# 15V_PowerSupply.net
KiCad netlist of a schematic drawn in Altium Designer
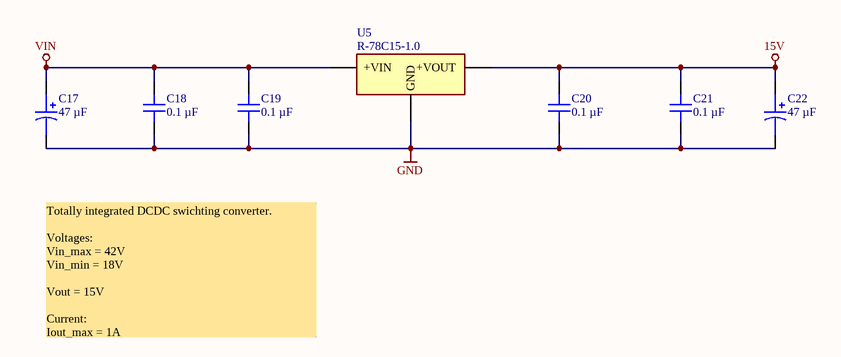
[diagram p0: 15V_PowerSupply.SchDoc]

(export (version "E")
  (design (tool "Eeschema 10.0.6"))
  (components
    (comp (ref "C17")
      (value "47 µF")
      (footprint "CAPAE830X650N")
      (description "Capacitor, 47µF, 35VDC Al Electrolyt")
      (fields
        (field (name "MANUFACTURER PART NUMBER") "EEE-1VA470P")
        (field (name "MANUFACTURER") "Panasonic")
        (field (name "CREATED FROM") "T. Wendt")
      )
      (libsource (lib "user") (part "CAPACITOR_POLARIZED_EEE"))
    )
    (comp (ref "C18")
      (value "0.1 µF")
      (footprint "C_0603")
      (description "Capacitor 0603, 50 VDC, 0.1 µF, X7R")
      (fields
        (field (name "MANUFACTURER PART NUMBER") "C0603X104K5RAC7411")
        (field (name "MANUFACTURER") "KEMET")
        (field (name "CREATED FROM") "MGremer")
      )
      (libsource (lib "user") (part "Capacitor"))
    )
    (comp (ref "C19")
      (value "0.1 µF")
      (footprint "C_0603")
      (description "Capacitor 0603, 50 VDC, 0.1 µF, X7R")
      (fields
        (field (name "MANUFACTURER PART NUMBER") "C0603X104K5RAC7411")
        (field (name "MANUFACTURER") "KEMET")
        (field (name "CREATED FROM") "MGremer")
      )
      (libsource (lib "user") (part "Capacitor"))
    )
    (comp (ref "C20")
      (value "0.1 µF")
      (footprint "C_0603")
      (description "Capacitor 0603, 50 VDC, 0.1 µF, X7R")
      (fields
        (field (name "MANUFACTURER PART NUMBER") "C0603X104K5RAC7411")
        (field (name "MANUFACTURER") "KEMET")
        (field (name "CREATED FROM") "MGremer")
      )
      (libsource (lib "user") (part "Capacitor"))
    )
    (comp (ref "C21")
      (value "0.1 µF")
      (footprint "C_0603")
      (description "Capacitor 0603, 50 VDC, 0.1 µF, X7R")
      (fields
        (field (name "MANUFACTURER PART NUMBER") "C0603X104K5RAC7411")
        (field (name "MANUFACTURER") "KEMET")
        (field (name "CREATED FROM") "MGremer")
      )
      (libsource (lib "user") (part "Capacitor"))
    )
    (comp (ref "C22")
      (value "47 µF")
      (footprint "CAPAE830X650N")
      (description "Capacitor, 47µF, 35VDC Al Electrolyt")
      (fields
        (field (name "MANUFACTURER PART NUMBER") "EEE-1VA470P")
        (field (name "MANUFACTURER") "Panasonic")
        (field (name "CREATED FROM") "T. Wendt")
      )
      (libsource (lib "user") (part "CAPACITOR_POLARIZED_EEE"))
    )
    (comp (ref "U5")
      (value "R-78C15-1.0")
      (footprint "R78C1510")
      (description "Not isolated DCDC Converter 15 V Output, 1 A, 18 - 42 V Input")
      (fields (field (name "MANUFACTURER") "RECOM") (field (name "CREATED FROM") "T. Wendt"))
      (libsource (lib "user") (part "R-78C5.0-1.0"))
    )
  )
  (nets
    (net (code "1") (name "15V") (class "Default")
      (node (ref "C20") (pin "2") (pinfunction "2_2") (pintype "passive"))
      (node (ref "C21") (pin "2") (pinfunction "2_2") (pintype "passive"))
      (node (ref "C22") (pin "1") (pinfunction "1_1") (pintype "passive"))
      (node (ref "U5") (pin "3") (pinfunction "+VOUT_3") (pintype "power_in"))
    )
    (net (code "2") (name "GND") (class "Default")
      (node (ref "C17") (pin "2") (pinfunction "2_2") (pintype "passive"))
      (node (ref "C18") (pin "1") (pinfunction "1_1") (pintype "passive"))
      (node (ref "C19") (pin "1") (pinfunction "1_1") (pintype "passive"))
      (node (ref "C20") (pin "1") (pinfunction "1_1") (pintype "passive"))
      (node (ref "C21") (pin "1") (pinfunction "1_1") (pintype "passive"))
      (node (ref "C22") (pin "2") (pinfunction "2_2") (pintype "passive"))
      (node (ref "U5") (pin "2") (pinfunction "GND_2") (pintype "passive"))
    )
    (net (code "3") (name "VIN") (class "Default")
      (node (ref "C17") (pin "1") (pinfunction "1_1") (pintype "passive"))
      (node (ref "C18") (pin "2") (pinfunction "2_2") (pintype "passive"))
      (node (ref "C19") (pin "2") (pinfunction "2_2") (pintype "passive"))
      (node (ref "U5") (pin "1") (pinfunction "+VIN_1") (pintype "power_in"))
    )
  )
)
